# CAN_USB_PIC32.net
KiCad netlist of a schematic drawn in EAGLE
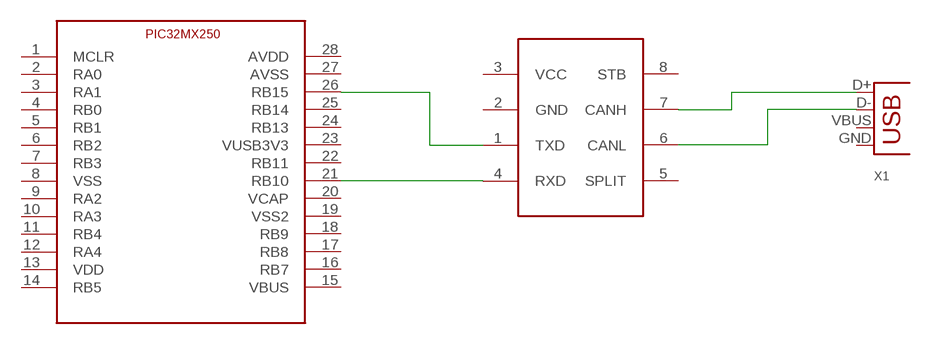
[diagram p0: schematic, sheet 1]

(export (version "E")
  (design (tool "Eeschema 10.0.6"))
  (components
    (comp (ref "U$1")
      (value "TJA1040")
      (footprint "eagle-import:SOIC8-N_MC")
      (libsource (lib "eagle-import") (part "TJA1040"))
    )
    (comp (ref "U$2")
      (value "PIC32MX250SOIC")
      (footprint "eagle-import:SOIC28")
      (libsource (lib "eagle-import") (part "PIC32MX250SOIC"))
    )
    (comp (ref "X1")
      (value "USB-B-H")
      (footprint "eagle-import:USB-B-H")
      (libsource (lib "eagle-import") (part "USB-B-H"))
    )
  )
  (nets
    (net (code "1") (name "/GND") (class "Default")
      (node (ref "U$1") (pin "2") (pinfunction "GND_2") (pintype "power_in"))
    )
    (net (code "2") (name "/VCC") (class "Default")
      (node (ref "U$1") (pin "3") (pinfunction "VCC_3") (pintype "power_in"))
    )
    (net (code "3") (name "/VDD") (class "Default")
      (node (ref "U$2") (pin "13") (pinfunction "VDD_13") (pintype "power_in"))
    )
    (net (code "4") (name "/VSS") (class "Default")
      (node (ref "U$2") (pin "8") (pinfunction "VSS_8") (pintype "power_in"))
    )
    (net (code "5") (name "Net-(U$1-CANH)") (class "Default")
      (node (ref "U$1") (pin "7") (pinfunction "CANH_7") (pintype "bidirectional"))
      (node (ref "X1") (pin "D+") (pinfunction "D+_D+") (pintype "bidirectional"))
    )
    (net (code "6") (name "Net-(U$1-CANL)") (class "Default")
      (node (ref "U$1") (pin "6") (pinfunction "CANL_6") (pintype "bidirectional"))
      (node (ref "X1") (pin "D-") (pinfunction "D-_D-") (pintype "bidirectional"))
    )
    (net (code "7") (name "Net-(U$1-RXD)") (class "Default")
      (node (ref "U$1") (pin "4") (pinfunction "RXD_4") (pintype "output"))
      (node (ref "U$2") (pin "21") (pinfunction "RB10_21") (pintype "bidirectional"))
    )
    (net (code "8") (name "Net-(U$1-TXD)") (class "Default")
      (node (ref "U$1") (pin "1") (pinfunction "TXD_1") (pintype "input"))
      (node (ref "U$2") (pin "26") (pinfunction "RB15_26") (pintype "bidirectional"))
    )
    (net (code "9") (name "unconnected-(U$1-SPLIT-Pad5)") (class "Default")
      (node (ref "U$1") (pin "5") (pinfunction "SPLIT_5") (pintype "bidirectional"))
    )
    (net (code "10") (name "unconnected-(U$1-STB-Pad8)") (class "Default")
      (node (ref "U$1") (pin "8") (pinfunction "STB_8") (pintype "bidirectional"))
    )
    (net (code "11") (name "unconnected-(U$2-AVDD-Pad28)") (class "Default")
      (node (ref "U$2") (pin "28") (pinfunction "AVDD_28") (pintype "bidirectional"))
    )
    (net (code "12") (name "unconnected-(U$2-AVSS-Pad27)") (class "Default")
      (node (ref "U$2") (pin "27") (pinfunction "AVSS_27") (pintype "bidirectional"))
    )
    (net (code "13") (name "unconnected-(U$2-MCLR-Pad1)") (class "Default")
      (node (ref "U$2") (pin "1") (pinfunction "MCLR_1") (pintype "bidirectional"))
    )
    (net (code "14") (name "unconnected-(U$2-RA0-Pad2)") (class "Default")
      (node (ref "U$2") (pin "2") (pinfunction "RA0_2") (pintype "bidirectional"))
    )
    (net (code "15") (name "unconnected-(U$2-RA1-Pad3)") (class "Default")
      (node (ref "U$2") (pin "3") (pinfunction "RA1_3") (pintype "bidirectional"))
    )
    (net (code "16") (name "unconnected-(U$2-RA2-Pad9)") (class "Default")
      (node (ref "U$2") (pin "9") (pinfunction "RA2_9") (pintype "bidirectional"))
    )
    (net (code "17") (name "unconnected-(U$2-RA3-Pad10)") (class "Default")
      (node (ref "U$2") (pin "10") (pinfunction "RA3_10") (pintype "bidirectional"))
    )
    (net (code "18") (name "unconnected-(U$2-RA4-Pad12)") (class "Default")
      (node (ref "U$2") (pin "12") (pinfunction "RA4_12") (pintype "bidirectional"))
    )
    (net (code "19") (name "unconnected-(U$2-RB0-Pad4)") (class "Default")
      (node (ref "U$2") (pin "4") (pinfunction "RB0_4") (pintype "bidirectional"))
    )
    (net (code "20") (name "unconnected-(U$2-RB1-Pad5)") (class "Default")
      (node (ref "U$2") (pin "5") (pinfunction "RB1_5") (pintype "bidirectional"))
    )
    (net (code "21") (name "unconnected-(U$2-RB2-Pad6)") (class "Default")
      (node (ref "U$2") (pin "6") (pinfunction "RB2_6") (pintype "bidirectional"))
    )
    (net (code "22") (name "unconnected-(U$2-RB3-Pad7)") (class "Default")
      (node (ref "U$2") (pin "7") (pinfunction "RB3_7") (pintype "bidirectional"))
    )
    (net (code "23") (name "unconnected-(U$2-RB4-Pad11)") (class "Default")
      (node (ref "U$2") (pin "11") (pinfunction "RB4_11") (pintype "bidirectional"))
    )
    (net (code "24") (name "unconnected-(U$2-RB5-Pad14)") (class "Default")
      (node (ref "U$2") (pin "14") (pinfunction "RB5_14") (pintype "bidirectional"))
    )
    (net (code "25") (name "unconnected-(U$2-RB7-Pad16)") (class "Default")
      (node (ref "U$2") (pin "16") (pinfunction "RB7_16") (pintype "bidirectional"))
    )
    (net (code "26") (name "unconnected-(U$2-RB8-Pad17)") (class "Default")
      (node (ref "U$2") (pin "17") (pinfunction "RB8_17") (pintype "bidirectional"))
    )
    (net (code "27") (name "unconnected-(U$2-RB9-Pad18)") (class "Default")
      (node (ref "U$2") (pin "18") (pinfunction "RB9_18") (pintype "bidirectional"))
    )
    (net (code "28") (name "unconnected-(U$2-RB11-Pad22)") (class "Default")
      (node (ref "U$2") (pin "22") (pinfunction "RB11_22") (pintype "bidirectional"))
    )
    (net (code "29") (name "unconnected-(U$2-RB13-Pad24)") (class "Default")
      (node (ref "U$2") (pin "24") (pinfunction "RB13_24") (pintype "bidirectional"))
    )
    (net (code "30") (name "unconnected-(U$2-RB14-Pad25)") (class "Default")
      (node (ref "U$2") (pin "25") (pinfunction "RB14_25") (pintype "bidirectional"))
    )
    (net (code "31") (name "unconnected-(U$2-VBUS-Pad15)") (class "Default")
      (node (ref "U$2") (pin "15") (pinfunction "VBUS_15") (pintype "bidirectional"))
    )
    (net (code "32") (name "unconnected-(U$2-VCAP-Pad20)") (class "Default")
      (node (ref "U$2") (pin "20") (pinfunction "VCAP_20") (pintype "bidirectional"))
    )
    (net (code "33") (name "unconnected-(U$2-VSS2-Pad19)") (class "Default")
      (node (ref "U$2") (pin "19") (pinfunction "VSS2_19") (pintype "bidirectional"))
    )
    (net (code "34") (name "unconnected-(U$2-VUSB3V3-Pad23)") (class "Default")
      (node (ref "U$2") (pin "23") (pinfunction "VUSB3V3_23") (pintype "bidirectional"))
    )
    (net (code "35") (name "unconnected-(X1-PadGND)") (class "Default")
      (node (ref "X1") (pin "GND") (pinfunction "GND_GND") (pintype "bidirectional"))
    )
    (net (code "36") (name "unconnected-(X1-PadVBUS)") (class "Default")
      (node (ref "X1") (pin "VBUS") (pinfunction "VBUS_VBUS") (pintype "bidirectional"))
    )
  )
)
